# rx.net
KiCad netlist of a schematic drawn in Altium Designer
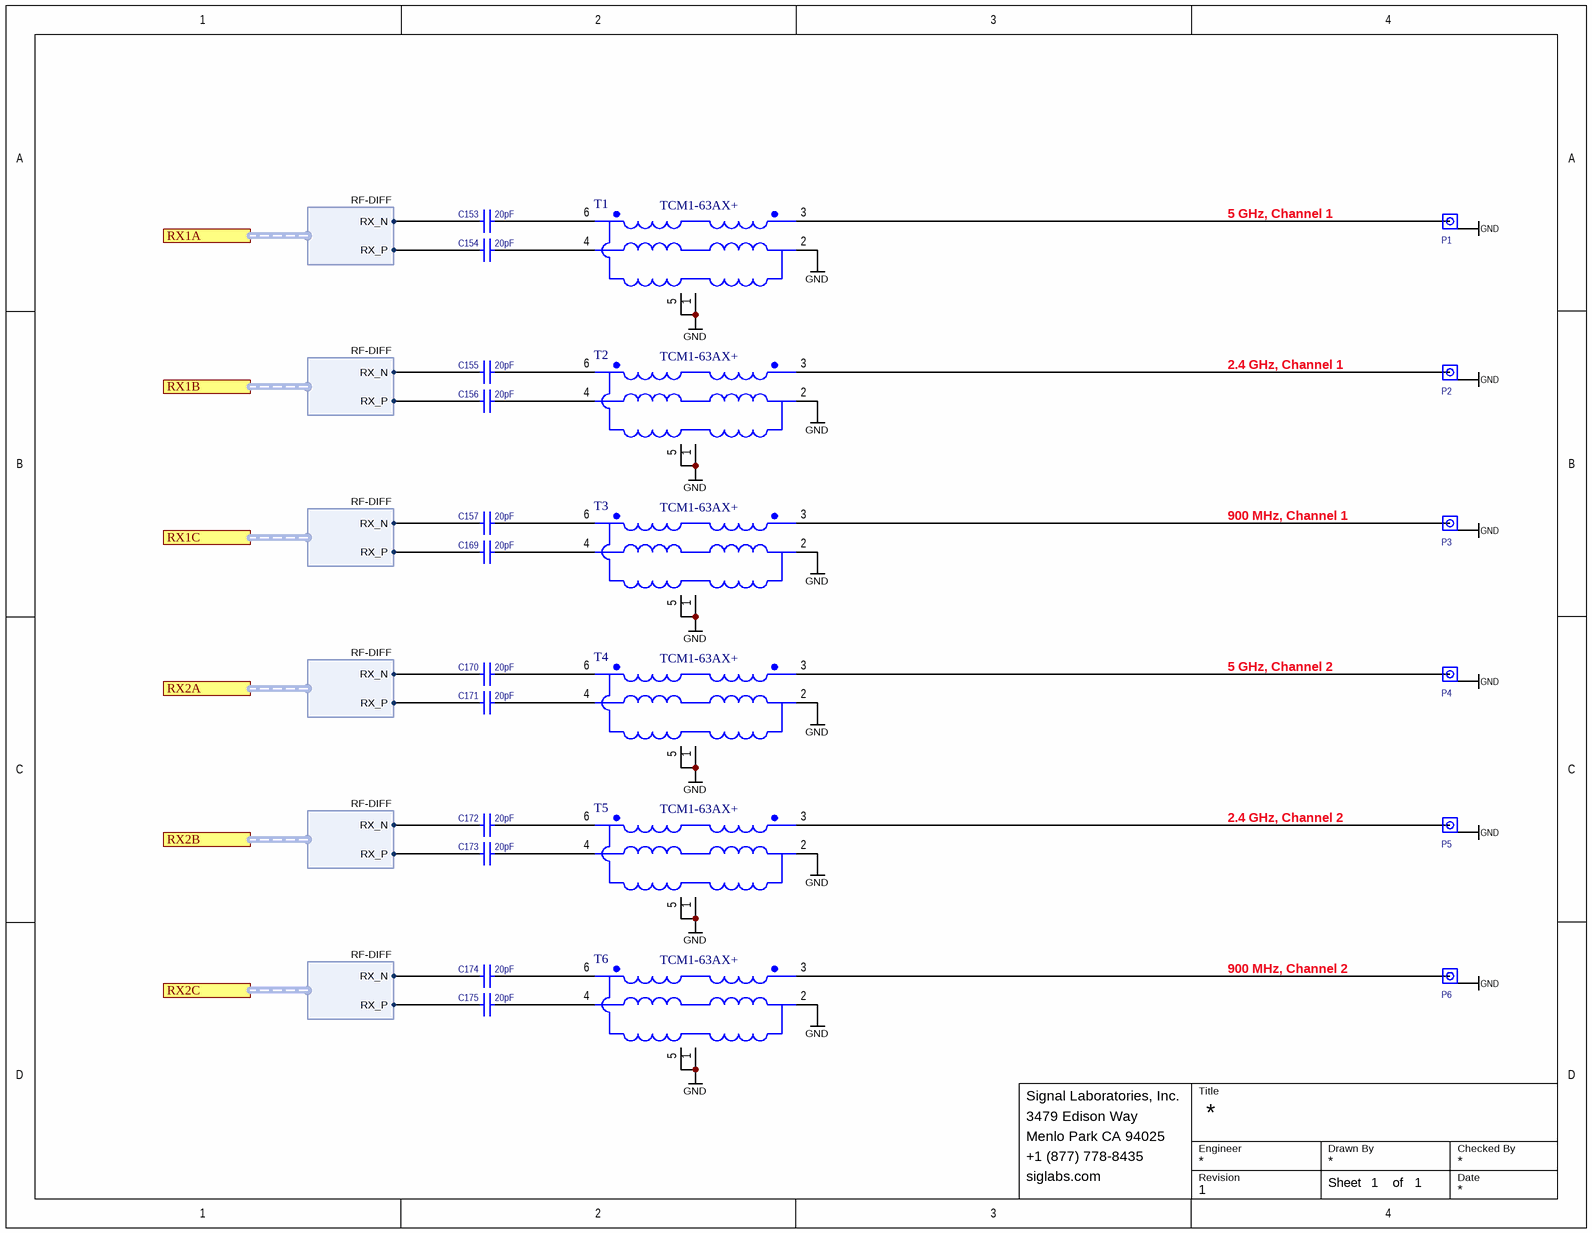
[diagram p0: rx.SchDoc]

(export (version "E")
  (design (tool "Eeschema 10.0.6"))
  (components
    (comp (ref "C153")
      (value "20pF")
      (footprint "generic:0402")
      (description "Ceramic Capacitor 20pF ±1% 50V NP0 0402")
      (fields (field (name "VOLTAGE") "50V") (field (name "MANUFACTURER") "Kemet"))
      (libsource (lib "PopRock") (part "CAP 0402"))
    )
    (comp (ref "C154")
      (value "20pF")
      (footprint "generic:0402")
      (description "Ceramic Capacitor 20pF ±1% 50V NP0 0402")
      (fields (field (name "VOLTAGE") "50V") (field (name "MANUFACTURER") "Kemet"))
      (libsource (lib "PopRock") (part "CAP 0402"))
    )
    (comp (ref "C155")
      (value "20pF")
      (footprint "generic:0402")
      (description "Ceramic Capacitor 20pF ±1% 50V NP0 0402")
      (fields (field (name "VOLTAGE") "50V") (field (name "MANUFACTURER") "Kemet"))
      (libsource (lib "PopRock") (part "CAP 0402"))
    )
    (comp (ref "C156")
      (value "20pF")
      (footprint "generic:0402")
      (description "Ceramic Capacitor 20pF ±1% 50V NP0 0402")
      (fields (field (name "VOLTAGE") "50V") (field (name "MANUFACTURER") "Kemet"))
      (libsource (lib "PopRock") (part "CAP 0402"))
    )
    (comp (ref "C157")
      (value "20pF")
      (footprint "generic:0402")
      (description "Ceramic Capacitor 20pF ±1% 50V NP0 0402")
      (fields (field (name "VOLTAGE") "50V") (field (name "MANUFACTURER") "Kemet"))
      (libsource (lib "PopRock") (part "CAP 0402"))
    )
    (comp (ref "C169")
      (value "20pF")
      (footprint "generic:0402")
      (description "Ceramic Capacitor 20pF ±1% 50V NP0 0402")
      (fields (field (name "VOLTAGE") "50V") (field (name "MANUFACTURER") "Kemet"))
      (libsource (lib "PopRock") (part "CAP 0402"))
    )
    (comp (ref "C170")
      (value "20pF")
      (footprint "generic:0402")
      (description "Ceramic Capacitor 20pF ±1% 50V NP0 0402")
      (fields (field (name "VOLTAGE") "50V") (field (name "MANUFACTURER") "Kemet"))
      (libsource (lib "PopRock") (part "CAP 0402"))
    )
    (comp (ref "C171")
      (value "20pF")
      (footprint "generic:0402")
      (description "Ceramic Capacitor 20pF ±1% 50V NP0 0402")
      (fields (field (name "VOLTAGE") "50V") (field (name "MANUFACTURER") "Kemet"))
      (libsource (lib "PopRock") (part "CAP 0402"))
    )
    (comp (ref "C172")
      (value "20pF")
      (footprint "generic:0402")
      (description "Ceramic Capacitor 20pF ±1% 50V NP0 0402")
      (fields (field (name "VOLTAGE") "50V") (field (name "MANUFACTURER") "Kemet"))
      (libsource (lib "PopRock") (part "CAP 0402"))
    )
    (comp (ref "C173")
      (value "20pF")
      (footprint "generic:0402")
      (description "Ceramic Capacitor 20pF ±1% 50V NP0 0402")
      (fields (field (name "VOLTAGE") "50V") (field (name "MANUFACTURER") "Kemet"))
      (libsource (lib "PopRock") (part "CAP 0402"))
    )
    (comp (ref "C174")
      (value "20pF")
      (footprint "generic:0402")
      (description "Ceramic Capacitor 20pF ±1% 50V NP0 0402")
      (fields (field (name "VOLTAGE") "50V") (field (name "MANUFACTURER") "Kemet"))
      (libsource (lib "PopRock") (part "CAP 0402"))
    )
    (comp (ref "C175")
      (value "20pF")
      (footprint "generic:0402")
      (description "Ceramic Capacitor 20pF ±1% 50V NP0 0402")
      (fields (field (name "VOLTAGE") "50V") (field (name "MANUFACTURER") "Kemet"))
      (libsource (lib "PopRock") (part "CAP 0402"))
    )
    (comp (ref "P1")
      (value "U.FL-R-SMT(10)")
      (footprint "U.FL-R-SMT(10)")
      (description "Ultra Miniature Coaxial Jack, 50 Ohms")
      (fields (field (name "MANUFACTURER") "Hirose"))
      (libsource (lib "hirose") (part "U.FL-R-SMT(10)"))
    )
    (comp (ref "P2")
      (value "U.FL-R-SMT(10)")
      (footprint "U.FL-R-SMT(10)")
      (description "Ultra Miniature Coaxial Jack, 50 Ohms")
      (fields (field (name "MANUFACTURER") "Hirose"))
      (libsource (lib "hirose") (part "U.FL-R-SMT(10)"))
    )
    (comp (ref "P3")
      (value "U.FL-R-SMT(10)")
      (footprint "U.FL-R-SMT(10)")
      (description "Ultra Miniature Coaxial Jack, 50 Ohms")
      (fields (field (name "MANUFACTURER") "Hirose"))
      (libsource (lib "hirose") (part "U.FL-R-SMT(10)"))
    )
    (comp (ref "P4")
      (value "U.FL-R-SMT(10)")
      (footprint "U.FL-R-SMT(10)")
      (description "Ultra Miniature Coaxial Jack, 50 Ohms")
      (fields (field (name "MANUFACTURER") "Hirose"))
      (libsource (lib "hirose") (part "U.FL-R-SMT(10)"))
    )
    (comp (ref "P5")
      (value "U.FL-R-SMT(10)")
      (footprint "U.FL-R-SMT(10)")
      (description "Ultra Miniature Coaxial Jack, 50 Ohms")
      (fields (field (name "MANUFACTURER") "Hirose"))
      (libsource (lib "hirose") (part "U.FL-R-SMT(10)"))
    )
    (comp (ref "P6")
      (value "U.FL-R-SMT(10)")
      (footprint "U.FL-R-SMT(10)")
      (description "Ultra Miniature Coaxial Jack, 50 Ohms")
      (fields (field (name "MANUFACTURER") "Hirose"))
      (libsource (lib "hirose") (part "U.FL-R-SMT(10)"))
    )
    (comp (ref "T1")
      (value "TCM1-63AX+")
      (footprint "TCM1-63AX+")
      (description "RF Transformer 10-6000KHz")
      (fields (field (name "MANUFACTURER") "Mini-Circuits"))
      (libsource (lib "Mini-Circuits") (part "TCM1-63AX+"))
    )
    (comp (ref "T2")
      (value "TCM1-63AX+")
      (footprint "TCM1-63AX+")
      (description "RF Transformer 10-6000KHz")
      (fields (field (name "MANUFACTURER") "Mini-Circuits"))
      (libsource (lib "Mini-Circuits") (part "TCM1-63AX+"))
    )
    (comp (ref "T3")
      (value "TCM1-63AX+")
      (footprint "TCM1-63AX+")
      (description "RF Transformer 10-6000KHz")
      (fields (field (name "MANUFACTURER") "Mini-Circuits"))
      (libsource (lib "Mini-Circuits") (part "TCM1-63AX+"))
    )
    (comp (ref "T4")
      (value "TCM1-63AX+")
      (footprint "TCM1-63AX+")
      (description "RF Transformer 10-6000KHz")
      (fields (field (name "MANUFACTURER") "Mini-Circuits"))
      (libsource (lib "Mini-Circuits") (part "TCM1-63AX+"))
    )
    (comp (ref "T5")
      (value "TCM1-63AX+")
      (footprint "TCM1-63AX+")
      (description "RF Transformer 10-6000KHz")
      (fields (field (name "MANUFACTURER") "Mini-Circuits"))
      (libsource (lib "Mini-Circuits") (part "TCM1-63AX+"))
    )
    (comp (ref "T6")
      (value "TCM1-63AX+")
      (footprint "TCM1-63AX+")
      (description "RF Transformer 10-6000KHz")
      (fields (field (name "MANUFACTURER") "Mini-Circuits"))
      (libsource (lib "Mini-Circuits") (part "TCM1-63AX+"))
    )
  )
  (nets
    (net (code "3") (name "GND") (class "Default")
      (node (ref "P1") (pin "2") (pinfunction "GND_2") (pintype "passive"))
      (node (ref "P2") (pin "2") (pinfunction "GND_2") (pintype "passive"))
      (node (ref "P3") (pin "2") (pinfunction "GND_2") (pintype "passive"))
      (node (ref "P4") (pin "2") (pinfunction "GND_2") (pintype "passive"))
      (node (ref "P5") (pin "2") (pinfunction "GND_2") (pintype "passive"))
      (node (ref "P6") (pin "2") (pinfunction "GND_2") (pintype "passive"))
      (node (ref "T1") (pin "1") (pinfunction "1_1") (pintype "passive"))
      (node (ref "T1") (pin "2") (pinfunction "2_2") (pintype "passive"))
      (node (ref "T1") (pin "5") (pinfunction "5_5") (pintype "passive"))
      (node (ref "T2") (pin "1") (pinfunction "1_1") (pintype "passive"))
      (node (ref "T2") (pin "2") (pinfunction "2_2") (pintype "passive"))
      (node (ref "T2") (pin "5") (pinfunction "5_5") (pintype "passive"))
      (node (ref "T3") (pin "1") (pinfunction "1_1") (pintype "passive"))
      (node (ref "T3") (pin "2") (pinfunction "2_2") (pintype "passive"))
      (node (ref "T3") (pin "5") (pinfunction "5_5") (pintype "passive"))
      (node (ref "T4") (pin "1") (pinfunction "1_1") (pintype "passive"))
      (node (ref "T4") (pin "2") (pinfunction "2_2") (pintype "passive"))
      (node (ref "T4") (pin "5") (pinfunction "5_5") (pintype "passive"))
      (node (ref "T5") (pin "1") (pinfunction "1_1") (pintype "passive"))
      (node (ref "T5") (pin "2") (pinfunction "2_2") (pintype "passive"))
      (node (ref "T5") (pin "5") (pinfunction "5_5") (pintype "passive"))
      (node (ref "T6") (pin "1") (pinfunction "1_1") (pintype "passive"))
      (node (ref "T6") (pin "2") (pinfunction "2_2") (pintype "passive"))
      (node (ref "T6") (pin "5") (pinfunction "5_5") (pintype "passive"))
    )
    (net (code "4") (name "Net-(C153-Pad2)") (class "Default")
      (node (ref "C153") (pin "2") (pinfunction "2_2") (pintype "passive"))
      (node (ref "T1") (pin "6") (pinfunction "6_6") (pintype "passive"))
    )
    (net (code "5") (name "Net-(C154-Pad2)") (class "Default")
      (node (ref "C154") (pin "2") (pinfunction "2_2") (pintype "passive"))
      (node (ref "T1") (pin "4") (pinfunction "4_4") (pintype "passive"))
    )
    (net (code "6") (name "Net-(C155-Pad2)") (class "Default")
      (node (ref "C155") (pin "2") (pinfunction "2_2") (pintype "passive"))
      (node (ref "T2") (pin "6") (pinfunction "6_6") (pintype "passive"))
    )
    (net (code "7") (name "Net-(C156-Pad2)") (class "Default")
      (node (ref "C156") (pin "2") (pinfunction "2_2") (pintype "passive"))
      (node (ref "T2") (pin "4") (pinfunction "4_4") (pintype "passive"))
    )
    (net (code "8") (name "Net-(C157-Pad2)") (class "Default")
      (node (ref "C157") (pin "2") (pinfunction "2_2") (pintype "passive"))
      (node (ref "T3") (pin "6") (pinfunction "6_6") (pintype "passive"))
    )
    (net (code "9") (name "Net-(C169-Pad2)") (class "Default")
      (node (ref "C169") (pin "2") (pinfunction "2_2") (pintype "passive"))
      (node (ref "T3") (pin "4") (pinfunction "4_4") (pintype "passive"))
    )
    (net (code "10") (name "Net-(C170-Pad2)") (class "Default")
      (node (ref "C170") (pin "2") (pinfunction "2_2") (pintype "passive"))
      (node (ref "T4") (pin "6") (pinfunction "6_6") (pintype "passive"))
    )
    (net (code "11") (name "Net-(C171-Pad2)") (class "Default")
      (node (ref "C171") (pin "2") (pinfunction "2_2") (pintype "passive"))
      (node (ref "T4") (pin "4") (pinfunction "4_4") (pintype "passive"))
    )
    (net (code "12") (name "Net-(C172-Pad2)") (class "Default")
      (node (ref "C172") (pin "2") (pinfunction "2_2") (pintype "passive"))
      (node (ref "T5") (pin "6") (pinfunction "6_6") (pintype "passive"))
    )
    (net (code "13") (name "Net-(C173-Pad2)") (class "Default")
      (node (ref "C173") (pin "2") (pinfunction "2_2") (pintype "passive"))
      (node (ref "T5") (pin "4") (pinfunction "4_4") (pintype "passive"))
    )
    (net (code "14") (name "Net-(C174-Pad2)") (class "Default")
      (node (ref "C174") (pin "2") (pinfunction "2_2") (pintype "passive"))
      (node (ref "T6") (pin "6") (pinfunction "6_6") (pintype "passive"))
    )
    (net (code "15") (name "Net-(C175-Pad2)") (class "Default")
      (node (ref "C175") (pin "2") (pinfunction "2_2") (pintype "passive"))
      (node (ref "T6") (pin "4") (pinfunction "4_4") (pintype "passive"))
    )
    (net (code "16") (name "Net-(P1-RF)") (class "Default")
      (node (ref "P1") (pin "1") (pinfunction "RF_1") (pintype "passive"))
      (node (ref "T1") (pin "3") (pinfunction "3_3") (pintype "passive"))
    )
    (net (code "17") (name "Net-(P2-RF)") (class "Default")
      (node (ref "P2") (pin "1") (pinfunction "RF_1") (pintype "passive"))
      (node (ref "T2") (pin "3") (pinfunction "3_3") (pintype "passive"))
    )
    (net (code "18") (name "Net-(P3-RF)") (class "Default")
      (node (ref "P3") (pin "1") (pinfunction "RF_1") (pintype "passive"))
      (node (ref "T3") (pin "3") (pinfunction "3_3") (pintype "passive"))
    )
    (net (code "19") (name "Net-(P4-RF)") (class "Default")
      (node (ref "P4") (pin "1") (pinfunction "RF_1") (pintype "passive"))
      (node (ref "T4") (pin "3") (pinfunction "3_3") (pintype "passive"))
    )
    (net (code "20") (name "Net-(P5-RF)") (class "Default")
      (node (ref "P5") (pin "1") (pinfunction "RF_1") (pintype "passive"))
      (node (ref "T5") (pin "3") (pinfunction "3_3") (pintype "passive"))
    )
    (net (code "21") (name "Net-(P6-RF)") (class "Default")
      (node (ref "P6") (pin "1") (pinfunction "RF_1") (pintype "passive"))
      (node (ref "T6") (pin "3") (pinfunction "3_3") (pintype "passive"))
    )
    (net (code "22") (name "unconnected-(C153-Pad1)") (class "Default")
      (node (ref "C153") (pin "1") (pinfunction "1_1") (pintype "passive"))
    )
    (net (code "23") (name "unconnected-(C154-Pad1)") (class "Default")
      (node (ref "C154") (pin "1") (pinfunction "1_1") (pintype "passive"))
    )
    (net (code "24") (name "unconnected-(C155-Pad1)") (class "Default")
      (node (ref "C155") (pin "1") (pinfunction "1_1") (pintype "passive"))
    )
    (net (code "25") (name "unconnected-(C156-Pad1)") (class "Default")
      (node (ref "C156") (pin "1") (pinfunction "1_1") (pintype "passive"))
    )
    (net (code "26") (name "unconnected-(C157-Pad1)") (class "Default")
      (node (ref "C157") (pin "1") (pinfunction "1_1") (pintype "passive"))
    )
    (net (code "27") (name "unconnected-(C169-Pad1)") (class "Default")
      (node (ref "C169") (pin "1") (pinfunction "1_1") (pintype "passive"))
    )
    (net (code "28") (name "unconnected-(C170-Pad1)") (class "Default")
      (node (ref "C170") (pin "1") (pinfunction "1_1") (pintype "passive"))
    )
    (net (code "29") (name "unconnected-(C171-Pad1)") (class "Default")
      (node (ref "C171") (pin "1") (pinfunction "1_1") (pintype "passive"))
    )
    (net (code "30") (name "unconnected-(C172-Pad1)") (class "Default")
      (node (ref "C172") (pin "1") (pinfunction "1_1") (pintype "passive"))
    )
    (net (code "31") (name "unconnected-(C173-Pad1)") (class "Default")
      (node (ref "C173") (pin "1") (pinfunction "1_1") (pintype "passive"))
    )
    (net (code "32") (name "unconnected-(C174-Pad1)") (class "Default")
      (node (ref "C174") (pin "1") (pinfunction "1_1") (pintype "passive"))
    )
    (net (code "33") (name "unconnected-(C175-Pad1)") (class "Default")
      (node (ref "C175") (pin "1") (pinfunction "1_1") (pintype "passive"))
    )
  )
)
